# SingleSystem1.net
KiCad netlist of a schematic drawn in EAGLE
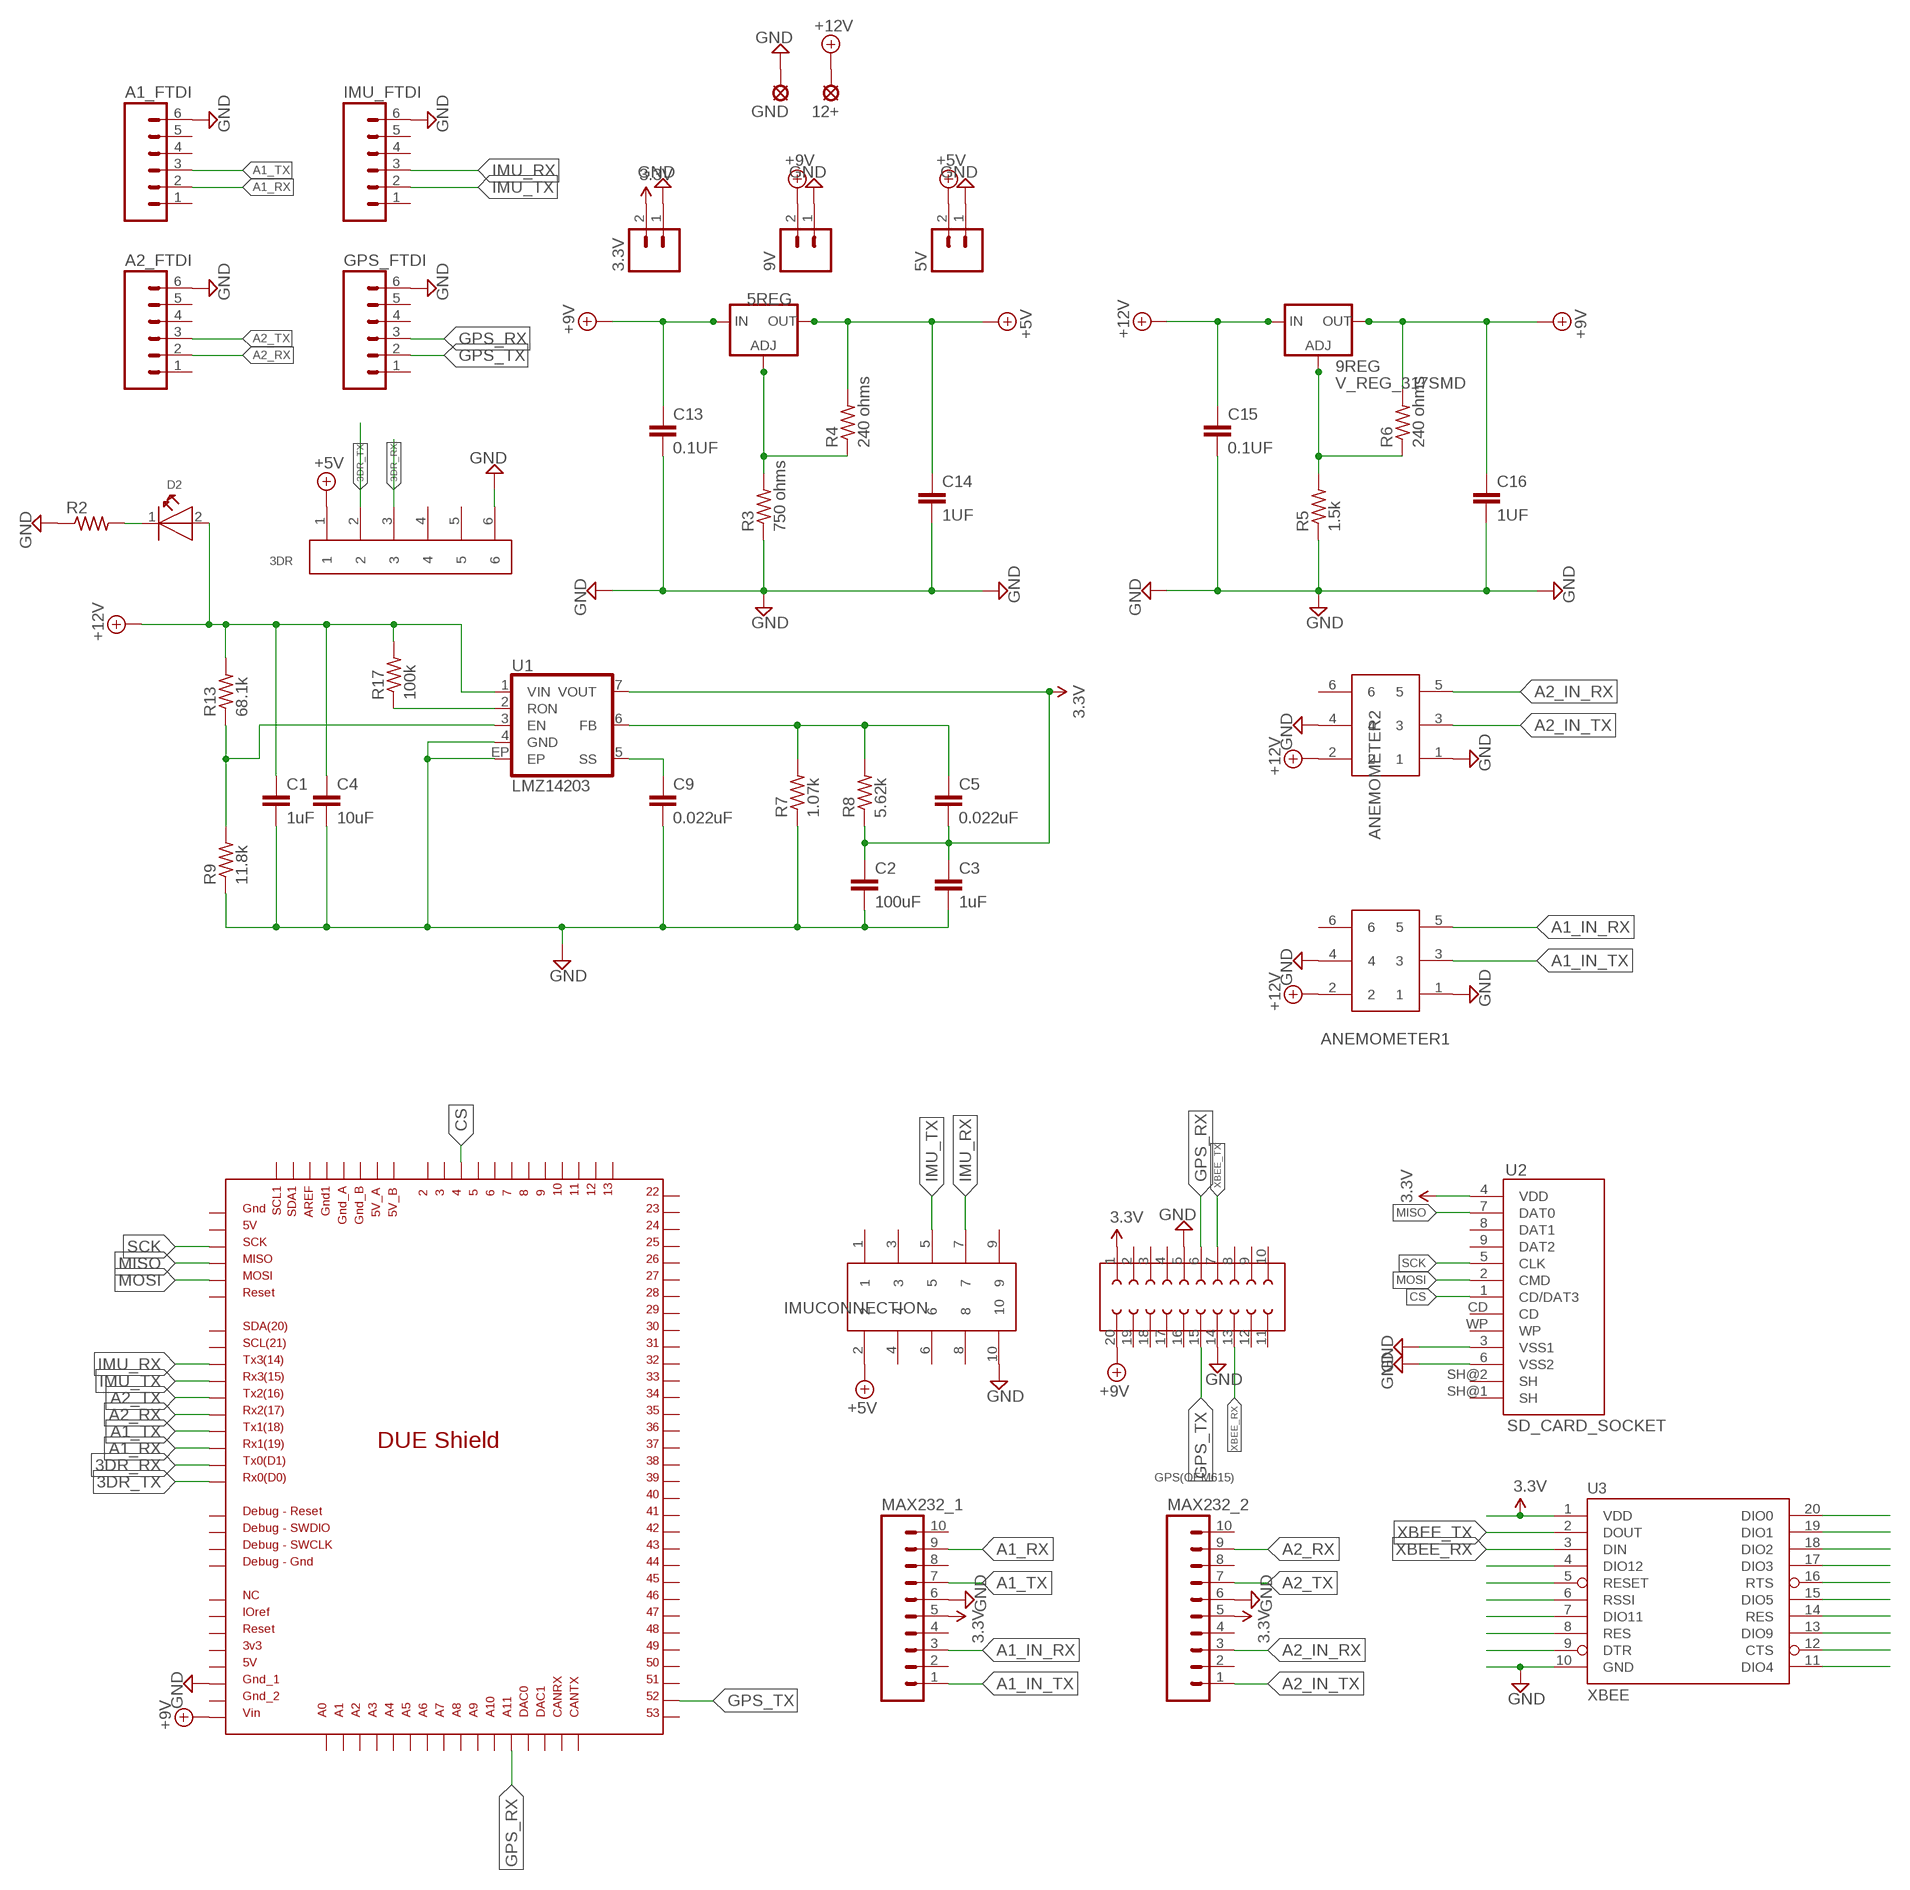
[diagram p0: schematic, sheet 1]

(export (version "E")
  (design (tool "Eeschema 10.0.6"))
  (components
    (comp (ref "3.3V")
      (value "M02")
      (footprint "eagle-import:02P")
      (libsource (lib "eagle-import") (part "M02"))
    )
    (comp (ref "3DR")
      (value "653006114822")
      (footprint "eagle-import:653006114822")
      (libsource (lib "eagle-import") (part "653006114822"))
    )
    (comp (ref "5REG")
      (value "V_REG_317SMD")
      (footprint "eagle-import:SOT223")
      (libsource (lib "eagle-import") (part "V_REG_317SMD"))
    )
    (comp (ref "5V")
      (value "M02")
      (footprint "eagle-import:02P")
      (libsource (lib "eagle-import") (part "M02"))
    )
    (comp (ref "9REG")
      (value "V_REG_317SMD")
      (footprint "eagle-import:SOT223")
      (libsource (lib "eagle-import") (part "V_REG_317SMD"))
    )
    (comp (ref "9V")
      (value "M02")
      (footprint "eagle-import:02P")
      (libsource (lib "eagle-import") (part "M02"))
    )
    (comp (ref "12+")
      (value "SE14")
      (footprint "eagle-import:SE14")
      (libsource (lib "eagle-import") (part "SE14"))
    )
    (comp (ref "A1_FTDI")
      (value "M06")
      (footprint "eagle-import:06P")
      (libsource (lib "eagle-import") (part "M06"))
    )
    (comp (ref "A2_FTDI")
      (value "M06")
      (footprint "eagle-import:06P")
      (libsource (lib "eagle-import") (part "M06"))
    )
    (comp (ref "ANEMOMETER1")
      (value "61200622323")
      (footprint "eagle-import:61200622323")
      (libsource (lib "eagle-import") (part "61200622323"))
    )
    (comp (ref "ANEMOMETER2")
      (value "61200622323")
      (footprint "eagle-import:61200622323")
      (libsource (lib "eagle-import") (part "61200622323"))
    )
    (comp (ref "C1")
      (value "1uF")
      (footprint "eagle-import:0805")
      (fields (field (name "MF") "VISHAY/SPRAGUE") (field (name "MPN") "1C10Z5U104M050R"))
      (libsource (lib "eagle-import") (part "1UF-25V-10%(0805)"))
    )
    (comp (ref "C2")
      (value "100uF")
      (footprint "eagle-import:1206")
      (libsource (lib "eagle-import") (part "CAP1206"))
    )
    (comp (ref "C3")
      (value "1uF")
      (footprint "eagle-import:0805")
      (fields (field (name "MF") "VISHAY/SPRAGUE") (field (name "MPN") "1C10Z5U104M050R"))
      (libsource (lib "eagle-import") (part "1UF-25V-10%(0805)"))
    )
    (comp (ref "C4")
      (value "10uF")
      (footprint "eagle-import:0805")
      (libsource (lib "eagle-import") (part "CAP0805"))
    )
    (comp (ref "C5")
      (value "0.022uF")
      (footprint "eagle-import:0603-CAP")
      (libsource (lib "eagle-import") (part "CAP0603-CAP"))
    )
    (comp (ref "C9")
      (value "0.022uF")
      (footprint "eagle-import:0603-CAP")
      (libsource (lib "eagle-import") (part "CAP0603-CAP"))
    )
    (comp (ref "C13")
      (value "0.1UF")
      (footprint "eagle-import:0805")
      (libsource (lib "eagle-import") (part "1UF-25V-10%(0805)"))
    )
    (comp (ref "C14")
      (value "1UF")
      (footprint "eagle-import:0805")
      (libsource (lib "eagle-import") (part "1UF-25V-10%(0805)"))
    )
    (comp (ref "C15")
      (value "0.1UF")
      (footprint "eagle-import:0805")
      (libsource (lib "eagle-import") (part "1UF-25V-10%(0805)"))
    )
    (comp (ref "C16")
      (value "1UF")
      (footprint "eagle-import:0805")
      (libsource (lib "eagle-import") (part "1UF-25V-10%(0805)"))
    )
    (comp (ref "D2")
      (value "WL-SMCW-150120BS75000-B")
      (footprint "eagle-import:1206")
      (fields
        (field (name "MANUFACTURER") "Würth Elektronik eiSos GmbH")
        (field (name "CREATED-BY") "Christin Otto")
      )
      (libsource (lib "eagle-import") (part "WL-SMCW-150120BS75000-B"))
    )
    (comp (ref "GND")
      (value "SE14")
      (footprint "eagle-import:SE14")
      (libsource (lib "eagle-import") (part "SE14"))
    )
    (comp (ref "GPS(OEM615)")
      (value "62002021821")
      (footprint "eagle-import:62002021821")
      (libsource (lib "eagle-import") (part "62002021821"))
    )
    (comp (ref "GPS_FTDI")
      (value "M06")
      (footprint "eagle-import:06P")
      (libsource (lib "eagle-import") (part "M06"))
    )
    (comp (ref "IMUCONNECTION")
      (value "62501021621")
      (footprint "eagle-import:62501021621")
      (libsource (lib "eagle-import") (part "62501021621"))
    )
    (comp (ref "IMU_FTDI")
      (value "M06")
      (footprint "eagle-import:06P")
      (libsource (lib "eagle-import") (part "M06"))
    )
    (comp (ref "MAX232_1")
      (value "M10")
      (footprint "eagle-import:10P")
      (libsource (lib "eagle-import") (part "M10"))
    )
    (comp (ref "MAX232_2")
      (value "M10")
      (footprint "eagle-import:10P")
      (libsource (lib "eagle-import") (part "M10"))
    )
    (comp (ref "R2")
      (value "R-US_M2012")
      (footprint "eagle-import:M2012")
      (libsource (lib "eagle-import") (part "resistor_R-US_M2012"))
    )
    (comp (ref "R3")
      (value "750 ohms")
      (footprint "eagle-import:M2012")
      (libsource (lib "eagle-import") (part "R-US_M2012"))
    )
    (comp (ref "R4")
      (value "240 ohms")
      (footprint "eagle-import:M2012")
      (libsource (lib "eagle-import") (part "R-US_M2012"))
    )
    (comp (ref "R5")
      (value "1.5k")
      (footprint "eagle-import:M2012")
      (libsource (lib "eagle-import") (part "R-US_M2012"))
    )
    (comp (ref "R6")
      (value "240 ohms")
      (footprint "eagle-import:M2012")
      (libsource (lib "eagle-import") (part "R-US_M2012"))
    )
    (comp (ref "R7")
      (value "1.07k")
      (footprint "eagle-import:M2012")
      (libsource (lib "eagle-import") (part "resistor_R-US_M2012"))
    )
    (comp (ref "R8")
      (value "5.62k")
      (footprint "eagle-import:M2012")
      (libsource (lib "eagle-import") (part "resistor_R-US_M2012"))
    )
    (comp (ref "R9")
      (value "11.8k")
      (footprint "eagle-import:M2012")
      (libsource (lib "eagle-import") (part "resistor_R-US_M2012"))
    )
    (comp (ref "R13")
      (value "68.1k")
      (footprint "eagle-import:M2012")
      (libsource (lib "eagle-import") (part "resistor_R-US_M2012"))
    )
    (comp (ref "R17")
      (value "100k")
      (footprint "eagle-import:M2012")
      (libsource (lib "eagle-import") (part "resistor_R-US_M2012"))
    )
    (comp (ref "U$1")
      (value "DUE(NORMAL)")
      (footprint "eagle-import:DUE(NORMAL)")
      (libsource (lib "eagle-import") (part "DUE(NORMAL)"))
    )
    (comp (ref "U1")
      (value "LMZ14203")
      (footprint "eagle-import:TO-PMOD-7")
      (libsource (lib "eagle-import") (part "LMZ14203"))
    )
    (comp (ref "U2")
      (value "SD_CARD_SOCKET")
      (footprint "eagle-import:SD_1_1")
      (libsource (lib "eagle-import") (part "SD_CARD_SOCKET"))
    )
    (comp (ref "U3")
      (value "XBEE")
      (footprint "eagle-import:XBEE-1")
      (libsource (lib "eagle-import") (part "XBEE-1B1"))
    )
  )
  (nets
    (net (code "1") (name "+5V") (class "Default")
      (node (ref "3DR") (pin "1") (pinfunction "1_1") (pintype "passive"))
      (node (ref "5REG") (pin "2") (pinfunction "OUT_2") (pintype "output"))
      (node (ref "5V") (pin "2") (pinfunction "2_2") (pintype "passive"))
      (node (ref "C14") (pin "1") (pinfunction "1_1") (pintype "passive"))
      (node (ref "IMUCONNECTION") (pin "2") (pinfunction "2_2") (pintype "passive"))
      (node (ref "R4") (pin "2") (pinfunction "2_2") (pintype "passive"))
    )
    (net (code "2") (name "+9V") (class "Default")
      (node (ref "5REG") (pin "3") (pinfunction "IN_3") (pintype "input"))
      (node (ref "9REG") (pin "2") (pinfunction "OUT_2") (pintype "output"))
      (node (ref "9V") (pin "2") (pinfunction "2_2") (pintype "passive"))
      (node (ref "C13") (pin "1") (pinfunction "1_1") (pintype "passive"))
      (node (ref "C16") (pin "1") (pinfunction "1_1") (pintype "passive"))
      (node (ref "GPS(OEM615)") (pin "20") (pinfunction "20_20") (pintype "passive"))
      (node (ref "R6") (pin "2") (pinfunction "2_2") (pintype "passive"))
      (node (ref "U$1") (pin "VIN") (pinfunction "VIN_VIN") (pintype "bidirectional"))
    )
    (net (code "3") (name "+12V") (class "Default")
      (node (ref "12+") (pin "MP") (pinfunction "MP_MP") (pintype "passive"))
      (node (ref "9REG") (pin "3") (pinfunction "IN_3") (pintype "input"))
      (node (ref "ANEMOMETER1") (pin "2") (pinfunction "2_2") (pintype "passive"))
      (node (ref "ANEMOMETER2") (pin "2") (pinfunction "2_2") (pintype "passive"))
      (node (ref "C1") (pin "1") (pinfunction "1_1") (pintype "passive"))
      (node (ref "C15") (pin "1") (pinfunction "1_1") (pintype "passive"))
      (node (ref "C4") (pin "1") (pinfunction "1_1") (pintype "passive"))
      (node (ref "D2") (pin "2") (pinfunction "A_2") (pintype "bidirectional"))
      (node (ref "R13") (pin "2") (pinfunction "2_2") (pintype "passive"))
      (node (ref "R17") (pin "2") (pinfunction "2_2") (pintype "passive"))
      (node (ref "U1") (pin "1") (pinfunction "VIN_1") (pintype "bidirectional"))
    )
    (net (code "4") (name "3.3V") (class "Default")
      (node (ref "3.3V") (pin "2") (pinfunction "2_2") (pintype "passive"))
      (node (ref "C2") (pin "1") (pinfunction "1_1") (pintype "passive"))
      (node (ref "C3") (pin "1") (pinfunction "1_1") (pintype "passive"))
      (node (ref "C5") (pin "2") (pinfunction "2_2") (pintype "passive"))
      (node (ref "GPS(OEM615)") (pin "1") (pinfunction "1_1") (pintype "passive"))
      (node (ref "MAX232_1") (pin "5") (pinfunction "5_5") (pintype "passive"))
      (node (ref "MAX232_2") (pin "5") (pinfunction "5_5") (pintype "passive"))
      (node (ref "R8") (pin "1") (pinfunction "1_1") (pintype "passive"))
      (node (ref "U1") (pin "7") (pinfunction "VOUT_7") (pintype "bidirectional"))
      (node (ref "U2") (pin "4") (pinfunction "VDD_4") (pintype "power_in"))
      (node (ref "U3") (pin "1") (pinfunction "VDD_1") (pintype "power_in"))
    )
    (net (code "5") (name "3DR_RX") (class "Default")
      (node (ref "3DR") (pin "3") (pinfunction "3_3") (pintype "passive"))
      (node (ref "U$1") (pin "TX0") (pinfunction "TX0_TX0") (pintype "bidirectional"))
    )
    (net (code "6") (name "3DR_TX") (class "Default")
      (node (ref "3DR") (pin "2") (pinfunction "2_2") (pintype "passive"))
      (node (ref "U$1") (pin "RX0") (pinfunction "RX0_RX0") (pintype "bidirectional"))
    )
    (net (code "7") (name "A1_IN_RX") (class "Default")
      (node (ref "ANEMOMETER1") (pin "5") (pinfunction "5_5") (pintype "passive"))
      (node (ref "MAX232_1") (pin "3") (pinfunction "3_3") (pintype "passive"))
    )
    (net (code "8") (name "A1_IN_TX") (class "Default")
      (node (ref "ANEMOMETER1") (pin "3") (pinfunction "3_3") (pintype "passive"))
      (node (ref "MAX232_1") (pin "1") (pinfunction "1_1") (pintype "passive"))
    )
    (net (code "9") (name "A1_RX") (class "Default")
      (node (ref "A1_FTDI") (pin "2") (pinfunction "2_2") (pintype "passive"))
      (node (ref "MAX232_1") (pin "9") (pinfunction "9_9") (pintype "passive"))
      (node (ref "U$1") (pin "RX1") (pinfunction "RX1_RX1") (pintype "bidirectional"))
    )
    (net (code "10") (name "A1_TX") (class "Default")
      (node (ref "A1_FTDI") (pin "3") (pinfunction "3_3") (pintype "passive"))
      (node (ref "MAX232_1") (pin "7") (pinfunction "7_7") (pintype "passive"))
      (node (ref "U$1") (pin "TX1") (pinfunction "TX1_TX1") (pintype "bidirectional"))
    )
    (net (code "11") (name "A2_IN_RX") (class "Default")
      (node (ref "ANEMOMETER2") (pin "5") (pinfunction "5_5") (pintype "passive"))
      (node (ref "MAX232_2") (pin "3") (pinfunction "3_3") (pintype "passive"))
    )
    (net (code "12") (name "A2_IN_TX") (class "Default")
      (node (ref "ANEMOMETER2") (pin "3") (pinfunction "3_3") (pintype "passive"))
      (node (ref "MAX232_2") (pin "1") (pinfunction "1_1") (pintype "passive"))
    )
    (net (code "13") (name "A2_RX") (class "Default")
      (node (ref "A2_FTDI") (pin "2") (pinfunction "2_2") (pintype "passive"))
      (node (ref "MAX232_2") (pin "9") (pinfunction "9_9") (pintype "passive"))
      (node (ref "U$1") (pin "RX2") (pinfunction "RX2_RX2") (pintype "bidirectional"))
    )
    (net (code "14") (name "A2_TX") (class "Default")
      (node (ref "A2_FTDI") (pin "3") (pinfunction "3_3") (pintype "passive"))
      (node (ref "MAX232_2") (pin "7") (pinfunction "7_7") (pintype "passive"))
      (node (ref "U$1") (pin "TX2") (pinfunction "TX2_TX2") (pintype "bidirectional"))
    )
    (net (code "15") (name "CS") (class "Default")
      (node (ref "U$1") (pin "4") (pinfunction "4_4") (pintype "bidirectional"))
      (node (ref "U2") (pin "1") (pinfunction "CD/DAT3_1") (pintype "bidirectional"))
    )
    (net (code "16") (name "GND") (class "Default")
      (node (ref "3.3V") (pin "1") (pinfunction "1_1") (pintype "passive"))
      (node (ref "3DR") (pin "6") (pinfunction "6_6") (pintype "passive"))
      (node (ref "5V") (pin "1") (pinfunction "1_1") (pintype "passive"))
      (node (ref "9V") (pin "1") (pinfunction "1_1") (pintype "passive"))
      (node (ref "A1_FTDI") (pin "6") (pinfunction "6_6") (pintype "passive"))
      (node (ref "A2_FTDI") (pin "6") (pinfunction "6_6") (pintype "passive"))
      (node (ref "ANEMOMETER1") (pin "1") (pinfunction "1_1") (pintype "passive"))
      (node (ref "ANEMOMETER1") (pin "4") (pinfunction "4_4") (pintype "passive"))
      (node (ref "ANEMOMETER2") (pin "1") (pinfunction "1_1") (pintype "passive"))
      (node (ref "ANEMOMETER2") (pin "4") (pinfunction "4_4") (pintype "passive"))
      (node (ref "C1") (pin "2") (pinfunction "2_2") (pintype "passive"))
      (node (ref "C13") (pin "2") (pinfunction "2_2") (pintype "passive"))
      (node (ref "C14") (pin "2") (pinfunction "2_2") (pintype "passive"))
      (node (ref "C15") (pin "2") (pinfunction "2_2") (pintype "passive"))
      (node (ref "C16") (pin "2") (pinfunction "2_2") (pintype "passive"))
      (node (ref "C2") (pin "2") (pinfunction "2_2") (pintype "passive"))
      (node (ref "C3") (pin "2") (pinfunction "2_2") (pintype "passive"))
      (node (ref "C4") (pin "2") (pinfunction "2_2") (pintype "passive"))
      (node (ref "C9") (pin "2") (pinfunction "2_2") (pintype "passive"))
      (node (ref "GND") (pin "MP") (pinfunction "MP_MP") (pintype "passive"))
      (node (ref "GPS(OEM615)") (pin "14") (pinfunction "14_14") (pintype "passive"))
      (node (ref "GPS(OEM615)") (pin "5") (pinfunction "5_5") (pintype "passive"))
      (node (ref "GPS_FTDI") (pin "6") (pinfunction "6_6") (pintype "passive"))
      (node (ref "IMUCONNECTION") (pin "10") (pinfunction "10_10") (pintype "passive"))
      (node (ref "IMU_FTDI") (pin "6") (pinfunction "6_6") (pintype "passive"))
      (node (ref "MAX232_1") (pin "6") (pinfunction "6_6") (pintype "passive"))
      (node (ref "MAX232_2") (pin "6") (pinfunction "6_6") (pintype "passive"))
      (node (ref "R2") (pin "1") (pinfunction "1_1") (pintype "passive"))
      (node (ref "R3") (pin "1") (pinfunction "1_1") (pintype "passive"))
      (node (ref "R5") (pin "1") (pinfunction "1_1") (pintype "passive"))
      (node (ref "R7") (pin "1") (pinfunction "1_1") (pintype "passive"))
      (node (ref "R9") (pin "1") (pinfunction "1_1") (pintype "passive"))
      (node (ref "U$1") (pin "GND_1") (pinfunction "GND_1_GND_1") (pintype "bidirectional"))
      (node (ref "U1") (pin "4") (pinfunction "GND_4") (pintype "bidirectional"))
      (node (ref "U1") (pin "EP") (pinfunction "EP_EP") (pintype "bidirectional"))
      (node (ref "U2") (pin "3") (pinfunction "VSS1_3") (pintype "power_in"))
      (node (ref "U2") (pin "6") (pinfunction "VSS2_6") (pintype "power_in"))
      (node (ref "U3") (pin "10") (pinfunction "GND_10") (pintype "power_in"))
    )
    (net (code "17") (name "GPS_RX") (class "Default")
      (node (ref "GPS(OEM615)") (pin "6") (pinfunction "6_6") (pintype "passive"))
      (node (ref "GPS_FTDI") (pin "3") (pinfunction "3_3") (pintype "passive"))
      (node (ref "U$1") (pin "A11") (pinfunction "A11_A11") (pintype "bidirectional"))
    )
    (net (code "18") (name "GPS_TX") (class "Default")
      (node (ref "GPS(OEM615)") (pin "15") (pinfunction "15_15") (pintype "passive"))
      (node (ref "GPS_FTDI") (pin "2") (pinfunction "2_2") (pintype "passive"))
      (node (ref "U$1") (pin "52") (pinfunction "52_52") (pintype "bidirectional"))
    )
    (net (code "19") (name "IMU_RX") (class "Default")
      (node (ref "IMUCONNECTION") (pin "7") (pinfunction "7_7") (pintype "passive"))
      (node (ref "IMU_FTDI") (pin "3") (pinfunction "3_3") (pintype "passive"))
      (node (ref "U$1") (pin "TX3") (pinfunction "TX3_TX3") (pintype "bidirectional"))
    )
    (net (code "20") (name "IMU_TX") (class "Default")
      (node (ref "IMUCONNECTION") (pin "5") (pinfunction "5_5") (pintype "passive"))
      (node (ref "IMU_FTDI") (pin "2") (pinfunction "2_2") (pintype "passive"))
      (node (ref "U$1") (pin "RX3") (pinfunction "RX3_RX3") (pintype "bidirectional"))
    )
    (net (code "21") (name "MISO") (class "Default")
      (node (ref "U$1") (pin "MISO_ICSP") (pinfunction "MISO_ICSP_MISO_ICSP") (pintype "bidirectional"))
      (node (ref "U2") (pin "7") (pinfunction "DAT0_7") (pintype "bidirectional"))
    )
    (net (code "22") (name "MOSI") (class "Default")
      (node (ref "U$1") (pin "MOSI_ICSP") (pinfunction "MOSI_ICSP_MOSI_ICSP") (pintype "bidirectional"))
      (node (ref "U2") (pin "2") (pinfunction "CMD_2") (pintype "bidirectional"))
    )
    (net (code "23") (name "Net-(5REG-ADJ)") (class "Default")
      (node (ref "5REG") (pin "1") (pinfunction "ADJ_1") (pintype "input"))
      (node (ref "R3") (pin "2") (pinfunction "2_2") (pintype "passive"))
      (node (ref "R4") (pin "1") (pinfunction "1_1") (pintype "passive"))
    )
    (net (code "24") (name "Net-(9REG-ADJ)") (class "Default")
      (node (ref "9REG") (pin "1") (pinfunction "ADJ_1") (pintype "input"))
      (node (ref "R5") (pin "2") (pinfunction "2_2") (pintype "passive"))
      (node (ref "R6") (pin "1") (pinfunction "1_1") (pintype "passive"))
    )
    (net (code "25") (name "Net-(D2-K)") (class "Default")
      (node (ref "D2") (pin "1") (pinfunction "K_1") (pintype "bidirectional"))
      (node (ref "R2") (pin "2") (pinfunction "2_2") (pintype "passive"))
    )
    (net (code "26") (name "Net-(U1-EN)") (class "Default")
      (node (ref "R13") (pin "1") (pinfunction "1_1") (pintype "passive"))
      (node (ref "R9") (pin "2") (pinfunction "2_2") (pintype "passive"))
      (node (ref "U1") (pin "3") (pinfunction "EN_3") (pintype "bidirectional"))
    )
    (net (code "27") (name "Net-(U1-FB)") (class "Default")
      (node (ref "C5") (pin "1") (pinfunction "1_1") (pintype "passive"))
      (node (ref "R7") (pin "2") (pinfunction "2_2") (pintype "passive"))
      (node (ref "R8") (pin "2") (pinfunction "2_2") (pintype "passive"))
      (node (ref "U1") (pin "6") (pinfunction "FB_6") (pintype "bidirectional"))
    )
    (net (code "28") (name "Net-(U1-RON)") (class "Default")
      (node (ref "R17") (pin "1") (pinfunction "1_1") (pintype "passive"))
      (node (ref "U1") (pin "2") (pinfunction "RON_2") (pintype "bidirectional"))
    )
    (net (code "29") (name "Net-(U1-SS)") (class "Default")
      (node (ref "C9") (pin "1") (pinfunction "1_1") (pintype "passive"))
      (node (ref "U1") (pin "5") (pinfunction "SS_5") (pintype "bidirectional"))
    )
    (net (code "30") (name "SCK") (class "Default")
      (node (ref "U$1") (pin "SCK_ICSP") (pinfunction "SCK_ICSP_SCK_ICSP") (pintype "bidirectional"))
      (node (ref "U2") (pin "5") (pinfunction "CLK_5") (pintype "bidirectional"))
    )
    (net (code "31") (name "XBEE_RX") (class "Default")
      (node (ref "GPS(OEM615)") (pin "13") (pinfunction "13_13") (pintype "passive"))
      (node (ref "U3") (pin "3") (pinfunction "DIN_3") (pintype "input"))
    )
    (net (code "32") (name "XBEE_TX") (class "Default")
      (node (ref "GPS(OEM615)") (pin "7") (pinfunction "7_7") (pintype "passive"))
      (node (ref "U3") (pin "2") (pinfunction "DOUT_2") (pintype "output"))
    )
    (net (code "33") (name "unconnected-(3DR-Pad4)") (class "Default")
      (node (ref "3DR") (pin "4") (pinfunction "4_4") (pintype "passive"))
    )
    (net (code "34") (name "unconnected-(3DR-Pad5)") (class "Default")
      (node (ref "3DR") (pin "5") (pinfunction "5_5") (pintype "passive"))
    )
    (net (code "35") (name "unconnected-(A1_FTDI-Pad1)") (class "Default")
      (node (ref "A1_FTDI") (pin "1") (pinfunction "1_1") (pintype "passive"))
    )
    (net (code "36") (name "unconnected-(A1_FTDI-Pad4)") (class "Default")
      (node (ref "A1_FTDI") (pin "4") (pinfunction "4_4") (pintype "passive"))
    )
    (net (code "37") (name "unconnected-(A1_FTDI-Pad5)") (class "Default")
      (node (ref "A1_FTDI") (pin "5") (pinfunction "5_5") (pintype "passive"))
    )
    (net (code "38") (name "unconnected-(A2_FTDI-Pad1)") (class "Default")
      (node (ref "A2_FTDI") (pin "1") (pinfunction "1_1") (pintype "passive"))
    )
    (net (code "39") (name "unconnected-(A2_FTDI-Pad4)") (class "Default")
      (node (ref "A2_FTDI") (pin "4") (pinfunction "4_4") (pintype "passive"))
    )
    (net (code "40") (name "unconnected-(A2_FTDI-Pad5)") (class "Default")
      (node (ref "A2_FTDI") (pin "5") (pinfunction "5_5") (pintype "passive"))
    )
    (net (code "41") (name "unconnected-(ANEMOMETER1-Pad6)") (class "Default")
      (node (ref "ANEMOMETER1") (pin "6") (pinfunction "6_6") (pintype "passive"))
    )
    (net (code "42") (name "unconnected-(ANEMOMETER2-Pad6)") (class "Default")
      (node (ref "ANEMOMETER2") (pin "6") (pinfunction "6_6") (pintype "passive"))
    )
    (net (code "43") (name "unconnected-(GPS(OEM615)-Pad2)") (class "Default")
      (node (ref "GPS(OEM615)") (pin "2") (pinfunction "2_2") (pintype "passive"))
    )
    (net (code "44") (name "unconnected-(GPS(OEM615)-Pad3)") (class "Default")
      (node (ref "GPS(OEM615)") (pin "3") (pinfunction "3_3") (pintype "passive"))
    )
    (net (code "45") (name "unconnected-(GPS(OEM615)-Pad4)") (class "Default")
      (node (ref "GPS(OEM615)") (pin "4") (pinfunction "4_4") (pintype "passive"))
    )
    (net (code "46") (name "unconnected-(GPS(OEM615)-Pad8)") (class "Default")
      (node (ref "GPS(OEM615)") (pin "8") (pinfunction "8_8") (pintype "passive"))
    )
    (net (code "47") (name "unconnected-(GPS(OEM615)-Pad9)") (class "Default")
      (node (ref "GPS(OEM615)") (pin "9") (pinfunction "9_9") (pintype "passive"))
    )
    (net (code "48") (name "unconnected-(GPS(OEM615)-Pad10)") (class "Default")
      (node (ref "GPS(OEM615)") (pin "10") (pinfunction "10_10") (pintype "passive"))
    )
    (net (code "49") (name "unconnected-(GPS(OEM615)-Pad11)") (class "Default")
      (node (ref "GPS(OEM615)") (pin "11") (pinfunction "11_11") (pintype "passive"))
    )
    (net (code "50") (name "unconnected-(GPS(OEM615)-Pad12)") (class "Default")
      (node (ref "GPS(OEM615)") (pin "12") (pinfunction "12_12") (pintype "passive"))
    )
    (net (code "51") (name "unconnected-(GPS(OEM615)-Pad16)") (class "Default")
      (node (ref "GPS(OEM615)") (pin "16") (pinfunction "16_16") (pintype "passive"))
    )
    (net (code "52") (name "unconnected-(GPS(OEM615)-Pad17)") (class "Default")
      (node (ref "GPS(OEM615)") (pin "17") (pinfunction "17_17") (pintype "passive"))
    )
    (net (code "53") (name "unconnected-(GPS(OEM615)-Pad18)") (class "Default")
      (node (ref "GPS(OEM615)") (pin "18") (pinfunction "18_18") (pintype "passive"))
    )
    (net (code "54") (name "unconnected-(GPS(OEM615)-Pad19)") (class "Default")
      (node (ref "GPS(OEM615)") (pin "19") (pinfunction "19_19") (pintype "passive"))
    )
    (net (code "55") (name "unconnected-(GPS_FTDI-Pad1)") (class "Default")
      (node (ref "GPS_FTDI") (pin "1") (pinfunction "1_1") (pintype "passive"))
    )
    (net (code "56") (name "unconnected-(GPS_FTDI-Pad4)") (class "Default")
      (node (ref "GPS_FTDI") (pin "4") (pinfunction "4_4") (pintype "passive"))
    )
    (net (code "57") (name "unconnected-(GPS_FTDI-Pad5)") (class "Default")
      (node (ref "GPS_FTDI") (pin "5") (pinfunction "5_5") (pintype "passive"))
    )
    (net (code "58") (name "unconnected-(IMUCONNECTION-Pad1)") (class "Default")
      (node (ref "IMUCONNECTION") (pin "1") (pinfunction "1_1") (pintype "passive"))
    )
    (net (code "59") (name "unconnected-(IMUCONNECTION-Pad3)") (class "Default")
      (node (ref "IMUCONNECTION") (pin "3") (pinfunction "3_3") (pintype "passive"))
    )
    (net (code "60") (name "unconnected-(IMUCONNECTION-Pad4)") (class "Default")
      (node (ref "IMUCONNECTION") (pin "4") (pinfunction "4_4") (pintype "passive"))
    )
    (net (code "61") (name "unconnected-(IMUCONNECTION-Pad6)") (class "Default")
      (node (ref "IMUCONNECTION") (pin "6") (pinfunction "6_6") (pintype "passive"))
    )
    (net (code "62") (name "unconnected-(IMUCONNECTION-Pad8)") (class "Default")
      (node (ref "IMUCONNECTION") (pin "8") (pinfunction "8_8") (pintype "passive"))
    )
    (net (code "63") (name "unconnected-(IMUCONNECTION-Pad9)") (class "Default")
      (node (ref "IMUCONNECTION") (pin "9") (pinfunction "9_9") (pintype "passive"))
    )
    (net (code "64") (name "unconnected-(IMU_FTDI-Pad1)") (class "Default")
      (node (ref "IMU_FTDI") (pin "1") (pinfunction "1_1") (pintype "passive"))
    )
    (net (code "65") (name "unconnected-(IMU_FTDI-Pad4)") (class "Default")
      (node (ref "IMU_FTDI") (pin "4") (pinfunction "4_4") (pintype "passive"))
    )
    (net (code "66") (name "unconnected-(IMU_FTDI-Pad5)") (class "Default")
      (node (ref "IMU_FTDI") (pin "5") (pinfunction "5_5") (pintype "passive"))
    )
    (net (code "67") (name "unconnected-(MAX232_1-Pad2)") (class "Default")
      (node (ref "MAX232_1") (pin "2") (pinfunction "2_2") (pintype "passive"))
    )
    (net (code "68") (name "unconnected-(MAX232_1-Pad4)") (class "Default")
      (node (ref "MAX232_1") (pin "4") (pinfunction "4_4") (pintype "passive"))
    )
    (net (code "69") (name "unconnected-(MAX232_1-Pad8)") (class "Default")
      (node (ref "MAX232_1") (pin "8") (pinfunction "8_8") (pintype "passive"))
    )
    (net (code "70") (name "unconnected-(MAX232_1-Pad10)") (class "Default")
      (node (ref "MAX232_1") (pin "10") (pinfunction "10_10") (pintype "passive"))
    )
    (net (code "71") (name "unconnected-(MAX232_2-Pad2)") (class "Default")
      (node (ref "MAX232_2") (pin "2") (pinfunction "2_2") (pintype "passive"))
    )
    (net (code "72") (name "unconnected-(MAX232_2-Pad4)") (class "Default")
      (node (ref "MAX232_2") (pin "4") (pinfunction "4_4") (pintype "passive"))
    )
    (net (code "73") (name "unconnected-(MAX232_2-Pad8)") (class "Default")
      (node (ref "MAX232_2") (pin "8") (pinfunction "8_8") (pintype "passive"))
    )
    (net (code "74") (name "unconnected-(MAX232_2-Pad10)") (class "Default")
      (node (ref "MAX232_2") (pin "10") (pinfunction "10_10") (pintype "passive"))
    )
    (net (code "75") (name "unconnected-(U$1-Pad2)") (class "Default")
      (node (ref "U$1") (pin "2") (pinfunction "2_2") (pintype "bidirectional"))
    )
    (net (code "76") (name "unconnected-(U$1-Pad3)") (class "Default")
      (node (ref "U$1") (pin "3") (pinfunction "3_3") (pintype "bidirectional"))
    )
    (net (code "77") (name "unconnected-(U$1-Pad3V3)") (class "Default")
      (node (ref "U$1") (pin "3V3") (pinfunction "3V3_3V3") (pintype "bidirectional"))
    )
    (net (code "78") (name "unconnected-(U$1-Pad5)") (class "Default")
      (node (ref "U$1") (pin "5") (pinfunction "5_5") (pintype "bidirectional"))
    )
    (net (code "79") (name "unconnected-(U$1-Pad5V)") (class "Default")
      (node (ref "U$1") (pin "5V") (pinfunction "5V_5V") (pintype "bidirectional"))
    )
    (net (code "80") (name "unconnected-(U$1-Pad5V_A)") (class "Default")
      (node (ref "U$1") (pin "5V_A") (pinfunction "5V_A_5V_A") (pintype "bidirectional"))
    )
    (net (code "81") (name "unconnected-(U$1-Pad5V_B)") (class "Default")
      (node (ref "U$1") (pin "5V_B") (pinfunction "5V_B_5V_B") (pintype "bidirectional"))
    )
    (net (code "82") (name "unconnected-(U$1-Pad5V_ICSP)") (class "Default")
      (node (ref "U$1") (pin "5V_ICSP") (pinfunction "5V_ICSP_5V_ICSP") (pintype "bidirectional"))
    )
    (net (code "83") (name "unconnected-(U$1-Pad6)") (class "Default")
      (node (ref "U$1") (pin "6") (pinfunction "6_6") (pintype "bidirectional"))
    )
    (net (code "84") (name "unconnected-(U$1-Pad7)") (class "Default")
      (node (ref "U$1") (pin "7") (pinfunction "7_7") (pintype "bidirectional"))
    )
    (net (code "85") (name "unconnected-(U$1-Pad8)") (class "Default")
      (node (ref "U$1") (pin "8") (pinfunction "8_8") (pintype "bidirectional"))
    )
    (net (code "86") (name "unconnected-(U$1-Pad9)") (class "Default")
      (node (ref "U$1") (pin "9") (pinfunction "9_9") (pintype "bidirectional"))
    )
    (net (code "87") (name "unconnected-(U$1-Pad10)") (class "Default")
      (node (ref "U$1") (pin "10") (pinfunction "10_10") (pintype "bidirectional"))
    )
    (net (code "88") (name "unconnected-(U$1-Pad11)") (class "Default")
      (node (ref "U$1") (pin "11") (pinfunction "11_11") (pintype "bidirectional"))
    )
    (net (code "89") (name "unconnected-(U$1-Pad12)") (class "Default")
      (node (ref "U$1") (pin "12") (pinfunction "12_12") (pintype "bidirectional"))
    )
    (net (code "90") (name "unconnected-(U$1-Pad13)") (class "Default")
      (node (ref "U$1") (pin "13") (pinfunction "13_13") (pintype "bidirectional"))
    )
    (net (code "91") (name "unconnected-(U$1-Pad22)") (class "Default")
      (node (ref "U$1") (pin "22") (pinfunction "22_22") (pintype "bidirectional"))
    )
    (net (code "92") (name "unconnected-(U$1-Pad23)") (class "Default")
      (node (ref "U$1") (pin "23") (pinfunction "23_23") (pintype "bidirectional"))
    )
    (net (code "93") (name "unconnected-(U$1-Pad24)") (class "Default")
      (node (ref "U$1") (pin "24") (pinfunction "24_24") (pintype "bidirectional"))
    )
    (net (code "94") (name "unconnected-(U$1-Pad25)") (class "Default")
      (node (ref "U$1") (pin "25") (pinfunction "25_25") (pintype "bidirectional"))
    )
    (net (code "95") (name "unconnected-(U$1-Pad26)") (class "Default")
      (node (ref "U$1") (pin "26") (pinfunction "26_26") (pintype "bidirectional"))
    )
    (net (code "96") (name "unconnected-(U$1-Pad27)") (class "Default")
      (node (ref "U$1") (pin "27") (pinfunction "27_27") (pintype "bidirectional"))
    )
    (net (code "97") (name "unconnected-(U$1-Pad28)") (class "Default")
      (node (ref "U$1") (pin "28") (pinfunction "28_28") (pintype "bidirectional"))
    )
    (net (code "98") (name "unconnected-(U$1-Pad29)") (class "Default")
      (node (ref "U$1") (pin "29") (pinfunction "29_29") (pintype "bidirectional"))
    )
    (net (code "99") (name "unconnected-(U$1-Pad30)") (class "Default")
      (node (ref "U$1") (pin "30") (pinfunction "30_30") (pintype "bidirectional"))
    )
    (net (code "100") (name "unconnected-(U$1-Pad31)") (class "Default")
      (node (ref "U$1") (pin "31") (pinfunction "31_31") (pintype "bidirectional"))
    )
    (net (code "101") (name "unconnected-(U$1-Pad32)") (class "Default")
      (node (ref "U$1") (pin "32") (pinfunction "32_32") (pintype "bidirectional"))
    )
    (net (code "102") (name "unconnected-(U$1-Pad33)") (class "Default")
      (node (ref "U$1") (pin "33") (pinfunction "33_33") (pintype "bidirectional"))
    )
    (net (code "103") (name "unconnected-(U$1-Pad34)") (class "Default")
      (node (ref "U$1") (pin "34") (pinfunction "34_34") (pintype "bidirectional"))
    )
    (net (code "104") (name "unconnected-(U$1-Pad35)") (class "Default")
      (node (ref "U$1") (pin "35") (pinfunction "35_35") (pintype "bidirectional"))
    )
    (net (code "105") (name "unconnected-(U$1-Pad36)") (class "Default")
      (node (ref "U$1") (pin "36") (pinfunction "36_36") (pintype "bidirectional"))
    )
    (net (code "106") (name "unconnected-(U$1-Pad37)") (class "Default")
      (node (ref "U$1") (pin "37") (pinfunction "37_37") (pintype "bidirectional"))
    )
    (net (code "107") (name "unconnected-(U$1-Pad38)") (class "Default")
      (node (ref "U$1") (pin "38") (pinfunction "38_38") (pintype "bidirectional"))
    )
    (net (code "108") (name "unconnected-(U$1-Pad39)") (class "Default")
      (node (ref "U$1") (pin "39") (pinfunction "39_39") (pintype "bidirectional"))
    )
    (net (code "109") (name "unconnected-(U$1-Pad40)") (class "Default")
      (node (ref "U$1") (pin "40") (pinfunction "40_40") (pintype "bidirectional"))
    )
    (net (code "110") (name "unconnected-(U$1-Pad41)") (class "Default")
      (node (ref "U$1") (pin "41") (pinfunction "41_41") (pintype "bidirectional"))
    )
    (net (code "111") (name "unconnected-(U$1-Pad42)") (class "Default")
      (node (ref "U$1") (pin "42") (pinfunction "42_42") (pintype "bidirectional"))
    )
    (net (code "112") (name "unconnected-(U$1-Pad43)") (class "Default")
      (node (ref "U$1") (pin "43") (pinfunction "43_43") (pintype "bidirectional"))
    )
    (net (code "113") (name "unconnected-(U$1-Pad44)") (class "Default")
      (node (ref "U$1") (pin "44") (pinfunction "44_44") (pintype "bidirectional"))
    )
    (net (code "114") (name "unconnected-(U$1-Pad45)") (class "Default")
      (node (ref "U$1") (pin "45") (pinfunction "45_45") (pintype "bidirectional"))
    )
    (net (code "115") (name "unconnected-(U$1-Pad46)") (class "Default")
      (node (ref "U$1") (pin "46") (pinfunction "46_46") (pintype "bidirectional"))
    )
    (net (code "116") (name "unconnected-(U$1-Pad47)") (class "Default")
      (node (ref "U$1") (pin "47") (pinfunction "47_47") (pintype "bidirectional"))
    )
    (net (code "117") (name "unconnected-(U$1-Pad48)") (class "Default")
      (node (ref "U$1") (pin "48") (pinfunction "48_48") (pintype "bidirectional"))
    )
    (net (code "118") (name "unconnected-(U$1-Pad49)") (class "Default")
      (node (ref "U$1") (pin "49") (pinfunction "49_49") (pintype "bidirectional"))
    )
    (net (code "119") (name "unconnected-(U$1-Pad50)") (class "Default")
      (node (ref "U$1") (pin "50") (pinfunction "50_50") (pintype "bidirectional"))
    )
    (net (code "120") (name "unconnected-(U$1-Pad51)") (class "Default")
      (node (ref "U$1") (pin "51") (pinfunction "51_51") (pintype "bidirectional"))
    )
    (net (code "121") (name "unconnected-(U$1-Pad53)") (class "Default")
      (node (ref "U$1") (pin "53") (pinfunction "53_53") (pintype "bidirectional"))
    )
    (net (code "122") (name "unconnected-(U$1-PadA0)") (class "Default")
      (node (ref "U$1") (pin "A0") (pinfunction "A0_A0") (pintype "bidirectional"))
    )
    (net (code "123") (name "unconnected-(U$1-PadA1)") (class "Default")
      (node (ref "U$1") (pin "A1") (pinfunction "A1_A1") (pintype "bidirectional"))
    )
    (net (code "124") (name "unconnected-(U$1-PadA2)") (class "Default")
      (node (ref "U$1") (pin "A2") (pinfunction "A2_A2") (pintype "bidirectional"))
    )
    (net (code "125") (name "unconnected-(U$1-PadA3)") (class "Default")
      (node (ref "U$1") (pin "A3") (pinfunction "A3_A3") (pintype "bidirectional"))
    )
    (net (code "126") (name "unconnected-(U$1-PadA4)") (class "Default")
      (node (ref "U$1") (pin "A4") (pinfunction "A4_A4") (pintype "bidirectional"))
    )
    (net (code "127") (name "unconnected-(U$1-PadA5)") (class "Default")
      (node (ref "U$1") (pin "A5") (pinfunction "A5_A5") (pintype "bidirectional"))
    )
    (net (code "128") (name "unconnected-(U$1-PadA6)") (class "Default")
      (node (ref "U$1") (pin "A6") (pinfunction "A6_A6") (pintype "bidirectional"))
    )
    (net (code "129") (name "unconnected-(U$1-PadA7)") (class "Default")
      (node (ref "U$1") (pin "A7") (pinfunction "A7_A7") (pintype "bidirectional"))
    )
    (net (code "130") (name "unconnected-(U$1-PadA8)") (class "Default")
      (node (ref "U$1") (pin "A8") (pinfunction "A8_A8") (pintype "bidirectional"))
    )
    (net (code "131") (name "unconnected-(U$1-PadA9)") (class "Default")
      (node (ref "U$1") (pin "A9") (pinfunction "A9_A9") (pintype "bidirectional"))
    )
    (net (code "132") (name "unconnected-(U$1-PadA10)") (class "Default")
      (node (ref "U$1") (pin "A10") (pinfunction "A10_A10") (pintype "bidirectional"))
    )
    (net (code "133") (name "unconnected-(U$1-PadAREF)") (class "Default")
      (node (ref "U$1") (pin "AREF") (pinfunction "AREF_AREF") (pintype "bidirectional"))
    )
    (net (code "134") (name "unconnected-(U$1-PadCANRX)") (class "Default")
      (node (ref "U$1") (pin "CANRX") (pinfunction "CANRX_CANRX") (pintype "bidirectional"))
    )
    (net (code "135") (name "unconnected-(U$1-PadCANTX)") (class "Default")
      (node (ref "U$1") (pin "CANTX") (pinfunction "CANTX_CANTX") (pintype "bidirectional"))
    )
    (net (code "136") (name "unconnected-(U$1-PadDAC0)") (class "Default")
      (node (ref "U$1") (pin "DAC0") (pinfunction "DAC0_DAC0") (pintype "bidirectional"))
    )
    (net (code "137") (name "unconnected-(U$1-PadDAC1)") (class "Default")
      (node (ref "U$1") (pin "DAC1") (pinfunction "DAC1_DAC1") (pintype "bidirectional"))
    )
    (net (code "138") (name "unconnected-(U$1-PadGND1)") (class "Default")
      (node (ref "U$1") (pin "GND1") (pinfunction "GND1_GND1") (pintype "bidirectional"))
    )
    (net (code "139") (name "unconnected-(U$1-PadGND_2)") (class "Default")
      (node (ref "U$1") (pin "GND_2") (pinfunction "GND_2_GND_2") (pintype "bidirectional"))
    )
    (net (code "140") (name "unconnected-(U$1-PadGND_A)") (class "Default")
      (node (ref "U$1") (pin "GND_A") (pinfunction "GND_A_GND_A") (pintype "bidirectional"))
    )
    (net (code "141") (name "unconnected-(U$1-PadGND_B)") (class "Default")
      (node (ref "U$1") (pin "GND_B") (pinfunction "GND_B_GND_B") (pintype "bidirectional"))
    )
    (net (code "142") (name "unconnected-(U$1-PadGND_DEBUG)") (class "Default")
      (node (ref "U$1") (pin "GND_DEBUG") (pinfunction "GND_DEBUG_GND_DEBUG") (pintype "bidirectional"))
    )
    (net (code "143") (name "unconnected-(U$1-PadGND_ICSP)") (class "Default")
      (node (ref "U$1") (pin "GND_ICSP") (pinfunction "GND_ICSP_GND_ICSP") (pintype "bidirectional"))
    )
    (net (code "144") (name "unconnected-(U$1-PadIOREF)") (class "Default")
      (node (ref "U$1") (pin "IOREF") (pinfunction "IOREF_IOREF") (pintype "bidirectional"))
    )
    (net (code "145") (name "unconnected-(U$1-PadNC)") (class "Default")
      (node (ref "U$1") (pin "NC") (pinfunction "NC_NC") (pintype "bidirectional"))
    )
    (net (code "146") (name "unconnected-(U$1-PadRESET)") (class "Default")
      (node (ref "U$1") (pin "RESET") (pinfunction "RESET_RESET") (pintype "bidirectional"))
    )
    (net (code "147") (name "unconnected-(U$1-PadRESET_DEBUG)") (class "Default")
      (node (ref "U$1") (pin "RESET_DEBUG") (pinfunction "RESET_DEBUG_RESET_DEBUG") (pintype "bidirectional"))
    )
    (net (code "148") (name "unconnected-(U$1-PadRESET_ICSP)") (class "Default")
      (node (ref "U$1") (pin "RESET_ICSP") (pinfunction "RESET_ICSP_RESET_ICSP") (pintype "bidirectional"))
    )
    (net (code "149") (name "unconnected-(U$1-PadSCL)") (class "Default")
      (node (ref "U$1") (pin "SCL") (pinfunction "SCL_SCL") (pintype "bidirectional"))
    )
    (net (code "150") (name "unconnected-(U$1-PadSCL1)") (class "Default")
      (node (ref "U$1") (pin "SCL1") (pinfunction "SCL1_SCL1") (pintype "bidirectional"))
    )
    (net (code "151") (name "unconnected-(U$1-PadSDA)") (class "Default")
      (node (ref "U$1") (pin "SDA") (pinfunction "SDA_SDA") (pintype "bidirectional"))
    )
    (net (code "152") (name "unconnected-(U$1-PadSDA1)") (class "Default")
      (node (ref "U$1") (pin "SDA1") (pinfunction "SDA1_SDA1") (pintype "bidirectional"))
    )
    (net (code "153") (name "unconnected-(U$1-PadSWCLK_DEBUG)") (class "Default")
      (node (ref "U$1") (pin "SWCLK_DEBUG") (pinfunction "SWCLK_DEBUG_SWCLK_DEBUG") (pintype "bidirectional"))
    )
    (net (code "154") (name "unconnected-(U$1-PadSWDIO_DEBUG)") (class "Default")
      (node (ref "U$1") (pin "SWDIO_DEBUG") (pinfunction "SWDIO_DEBUG_SWDIO_DEBUG") (pintype "bidirectional"))
    )
    (net (code "155") (name "unconnected-(U2-DAT1-Pad8)") (class "Default")
      (node (ref "U2") (pin "8") (pinfunction "DAT1_8") (pintype "bidirectional"))
    )
    (net (code "156") (name "unconnected-(U2-DAT2-Pad9)") (class "Default")
      (node (ref "U2") (pin "9") (pinfunction "DAT2_9") (pintype "bidirectional"))
    )
    (net (code "157") (name "unconnected-(U2-PadCD)") (class "Default")
      (node (ref "U2") (pin "CD") (pinfunction "CD_CD") (pintype "bidirectional"))
    )
    (net (code "158") (name "unconnected-(U2-PadWP)") (class "Default")
      (node (ref "U2") (pin "WP") (pinfunction "WP_WP") (pintype "bidirectional"))
    )
    (net (code "159") (name "unconnected-(U2-SH-PadSH@1)") (class "Default")
      (node (ref "U2") (pin "SH@1") (pinfunction "SH_SH@1") (pintype "bidirectional"))
    )
    (net (code "160") (name "unconnected-(U2-SH-PadSH@2)") (class "Default")
      (node (ref "U2") (pin "SH@2") (pinfunction "SH_SH@2") (pintype "bidirectional"))
    )
    (net (code "161") (name "unconnected-(U3-CTS-Pad12)") (class "Default")
      (node (ref "U3") (pin "12") (pinfunction "CTS_12") (pintype "output"))
    )
    (net (code "162") (name "unconnected-(U3-DIO0-Pad20)") (class "Default")
      (node (ref "U3") (pin "20") (pinfunction "DIO0_20") (pintype "bidirectional"))
    )
    (net (code "163") (name "unconnected-(U3-DIO1-Pad19)") (class "Default")
      (node (ref "U3") (pin "19") (pinfunction "DIO1_19") (pintype "bidirectional"))
    )
    (net (code "164") (name "unconnected-(U3-DIO2-Pad18)") (class "Default")
      (node (ref "U3") (pin "18") (pinfunction "DIO2_18") (pintype "bidirectional"))
    )
    (net (code "165") (name "unconnected-(U3-DIO3-Pad17)") (class "Default")
      (node (ref "U3") (pin "17") (pinfunction "DIO3_17") (pintype "bidirectional"))
    )
    (net (code "166") (name "unconnected-(U3-DIO4-Pad11)") (class "Default")
      (node (ref "U3") (pin "11") (pinfunction "DIO4_11") (pintype "bidirectional"))
    )
    (net (code "167") (name "unconnected-(U3-DIO5-Pad15)") (class "Default")
      (node (ref "U3") (pin "15") (pinfunction "DIO5_15") (pintype "bidirectional"))
    )
    (net (code "168") (name "unconnected-(U3-DIO9-Pad13)") (class "Default")
      (node (ref "U3") (pin "13") (pinfunction "DIO9_13") (pintype "bidirectional"))
    )
    (net (code "169") (name "unconnected-(U3-DIO11-Pad7)") (class "Default")
      (node (ref "U3") (pin "7") (pinfunction "DIO11_7") (pintype "bidirectional"))
    )
    (net (code "170") (name "unconnected-(U3-DIO12-Pad4)") (class "Default")
      (node (ref "U3") (pin "4") (pinfunction "DIO12_4") (pintype "bidirectional"))
    )
    (net (code "171") (name "unconnected-(U3-DTR-Pad9)") (class "Default")
      (node (ref "U3") (pin "9") (pinfunction "DTR_9") (pintype "bidirectional"))
    )
    (net (code "172") (name "unconnected-(U3-RES-Pad8)") (class "Default")
      (node (ref "U3") (pin "8") (pinfunction "RES_8") (pintype "bidirectional"))
    )
    (net (code "173") (name "unconnected-(U3-RES-Pad14)") (class "Default")
      (node (ref "U3") (pin "14") (pinfunction "RES_14") (pintype "bidirectional"))
    )
    (net (code "174") (name "unconnected-(U3-RESET-Pad5)") (class "Default")
      (node (ref "U3") (pin "5") (pinfunction "RESET_5") (pintype "input"))
    )
    (net (code "175") (name "unconnected-(U3-RSSI-Pad6)") (class "Default")
      (node (ref "U3") (pin "6") (pinfunction "RSSI_6") (pintype "bidirectional"))
    )
    (net (code "176") (name "unconnected-(U3-RTS-Pad16)") (class "Default")
      (node (ref "U3") (pin "16") (pinfunction "RTS_16") (pintype "input"))
    )
  )
)
